# QSPI.net
KiCad netlist of a schematic drawn in Altium Designer
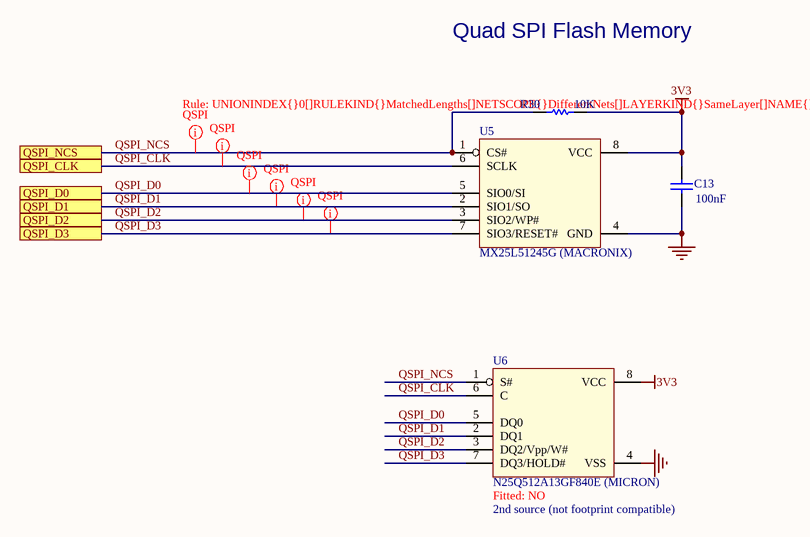
[diagram p0: QSPI.SchDoc]

(export (version "E")
  (design (tool "Eeschema 10.0.6"))
  (components
    (comp (ref "C13")
      (value "100nF")
      (footprint "0402C")
      (description "Capacitor,100nF,16V,X7R,10%,0402,YAGEO")
      (libsource (lib "MCD_TOOLS") (part "Cap_100nF_X7R_10%_0402"))
    )
    (comp (ref "R30")
      (value "10K")
      (footprint "0402R")
      (description "Resistor,10K,0402,1%,YAGEO")
      (libsource (lib "MCD_TOOLS") (part "Res_10K_1%_0402"))
    )
    (comp (ref "U5")
      (value "MX25L51245G (MACRONIX)")
      (footprint "SON8_1R27_6X8")
      (description "512Mb, 3V, Multiple I/O Serial Flash Memory, Quad/Dual")
      (fields (field (name "PROVIDED") "Subcon"))
      (libsource (lib "MCD_TOOLS_MISCELLANEOUS") (part "MX25L51245G"))
    )
    (comp (ref "U6")
      (value "N25Q512A13GF840E (MICRON)")
      (footprint "DFN8_1R27_6X8_TP4R6X5R3")
      (description "512Mb, 3V, Multiple I/O Serial Flash Memory, Quad/Dual")
      (fields (field (name "FITTED") "NO"))
      (libsource (lib "MCD_TOOLS_MISCELLANEOUS") (part "N25Q512A13GF840E"))
    )
  )
  (nets
    (net (code "1") (name "/QSPI_CLK") (class "Default")
      (node (ref "U5") (pin "6") (pinfunction "SCLK_6") (pintype "passive"))
      (node (ref "U6") (pin "6") (pinfunction "C_6") (pintype "passive"))
    )
    (net (code "2") (name "/QSPI_D0") (class "Default")
      (node (ref "U5") (pin "5") (pinfunction "SIO0/SI_5") (pintype "passive"))
      (node (ref "U6") (pin "5") (pinfunction "DQ0_5") (pintype "passive"))
    )
    (net (code "3") (name "/QSPI_D1") (class "Default")
      (node (ref "U5") (pin "2") (pinfunction "SIO1/SO_2") (pintype "passive"))
      (node (ref "U6") (pin "2") (pinfunction "DQ1_2") (pintype "passive"))
    )
    (net (code "4") (name "/QSPI_D2") (class "Default")
      (node (ref "U5") (pin "3") (pinfunction "SIO2/WP#_3") (pintype "passive"))
      (node (ref "U6") (pin "3") (pinfunction "DQ2/Vpp/W#_3") (pintype "passive"))
    )
    (net (code "5") (name "/QSPI_D3") (class "Default")
      (node (ref "U5") (pin "7") (pinfunction "SIO3/RESET#_7") (pintype "passive"))
      (node (ref "U6") (pin "7") (pinfunction "DQ3/HOLD#_7") (pintype "passive"))
    )
    (net (code "6") (name "/QSPI_NCS") (class "Default")
      (node (ref "R30") (pin "1") (pinfunction "1_1") (pintype "passive"))
      (node (ref "U5") (pin "1") (pinfunction "CS#_1") (pintype "passive"))
      (node (ref "U6") (pin "1") (pinfunction "S#_1") (pintype "passive"))
    )
    (net (code "7") (name "3V3") (class "Default")
      (node (ref "C13") (pin "2") (pinfunction "2_2") (pintype "passive"))
      (node (ref "R30") (pin "2") (pinfunction "2_2") (pintype "passive"))
      (node (ref "U5") (pin "8") (pinfunction "VCC_8") (pintype "passive"))
      (node (ref "U6") (pin "8") (pinfunction "VCC_8") (pintype "passive"))
    )
    (net (code "8") (name "GND") (class "Default")
      (node (ref "C13") (pin "1") (pinfunction "1_1") (pintype "passive"))
      (node (ref "U5") (pin "4") (pinfunction "GND_4") (pintype "passive"))
      (node (ref "U6") (pin "4") (pinfunction "VSS_4") (pintype "passive"))
    )
  )
)
